# 4_FPGA.net
KiCad netlist of a schematic drawn in Altium Designer
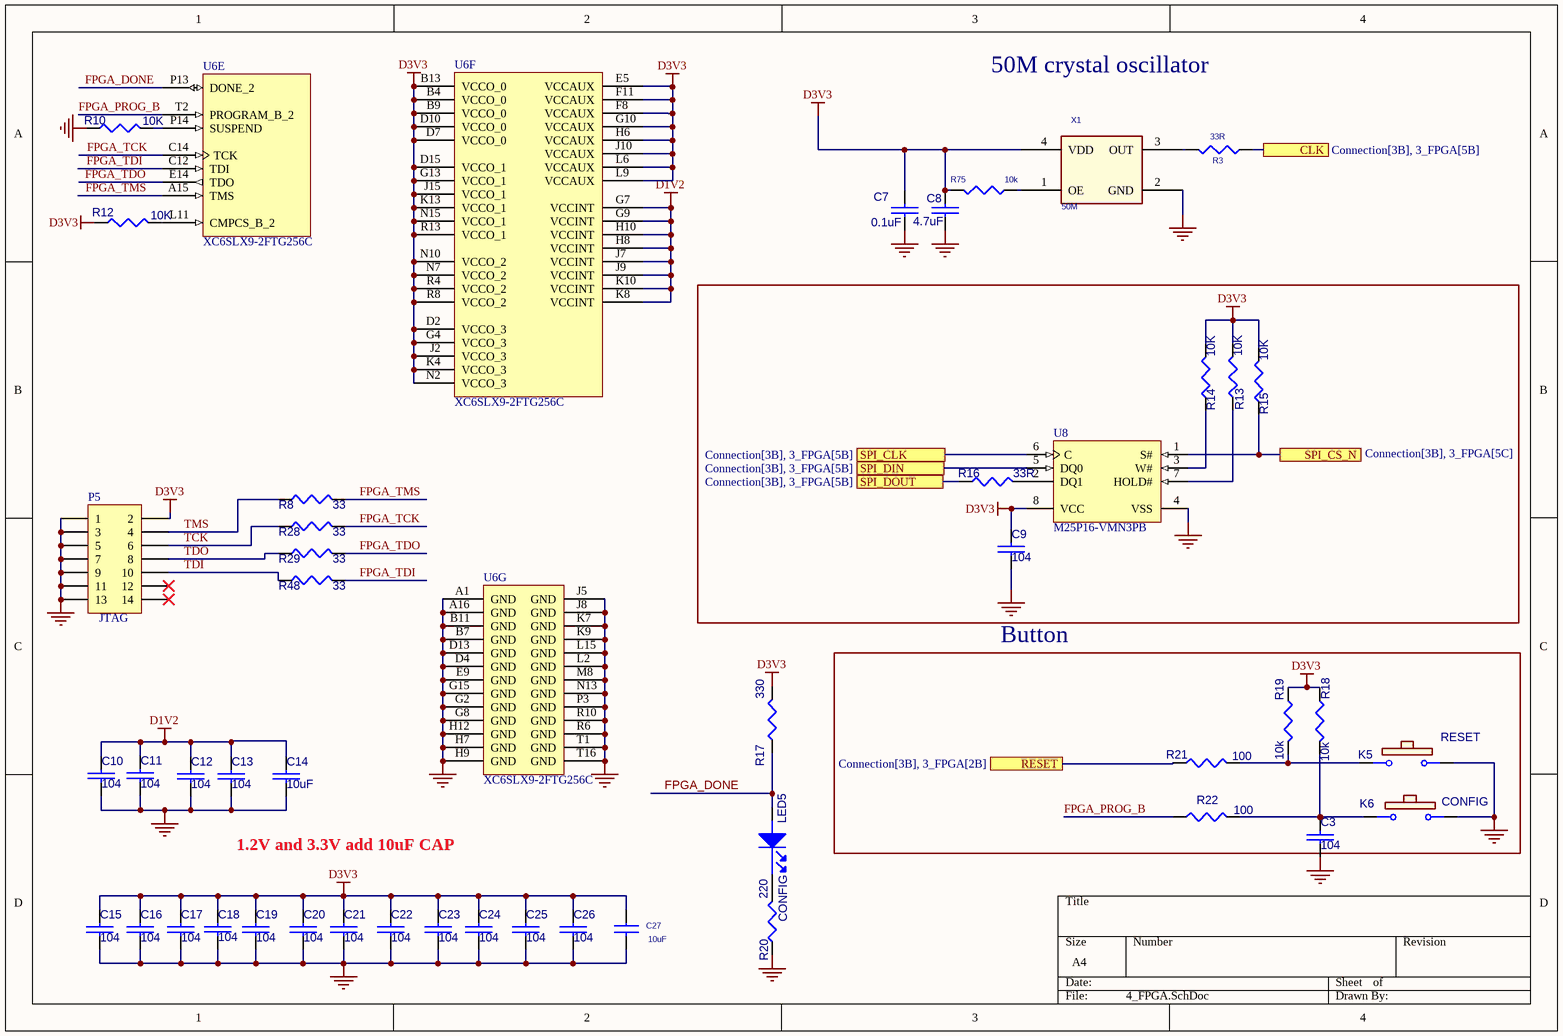
[diagram p0: 4_FPGA.SchDoc]

(export (version "E")
  (design (tool "Eeschema 10.0.6"))
  (components
    (comp (ref "C3") (value "104") (footprint "0402 Cap") (libsource (lib "SPARTAN6") (part "C_Dup2")))
    (comp (ref "C7") (value "0.1uF") (footprint "0402 Cap") (libsource (lib "SPARTAN6") (part "C_Dup2")))
    (comp (ref "C8") (value "4.7uF") (footprint "0402 Cap") (libsource (lib "SPARTAN6") (part "C_Dup2")))
    (comp (ref "C9") (value "104") (footprint "0402 Cap") (libsource (lib "SPARTAN6") (part "C_Dup2")))
    (comp (ref "C10") (value "104") (footprint "0402 Cap") (libsource (lib "SPARTAN6") (part "C_Dup2")))
    (comp (ref "C11") (value "104") (footprint "0402 Cap") (libsource (lib "SPARTAN6") (part "C_Dup2")))
    (comp (ref "C12") (value "104") (footprint "0402 Cap") (libsource (lib "SPARTAN6") (part "C_Dup2")))
    (comp (ref "C13") (value "104") (footprint "0402 Cap") (libsource (lib "SPARTAN6") (part "C_Dup2")))
    (comp (ref "C14") (value "10uF") (footprint "0402 Cap") (libsource (lib "SPARTAN6") (part "C_Dup2")))
    (comp (ref "C15") (value "104") (footprint "0402 Cap") (libsource (lib "SPARTAN6") (part "C_Dup2")))
    (comp (ref "C16") (value "104") (footprint "0402 Cap") (libsource (lib "SPARTAN6") (part "C_Dup2")))
    (comp (ref "C17") (value "104") (footprint "0402 Cap") (libsource (lib "SPARTAN6") (part "C_Dup2")))
    (comp (ref "C18") (value "104") (footprint "0402 Cap") (libsource (lib "SPARTAN6") (part "C_Dup2")))
    (comp (ref "C19") (value "104") (footprint "0402 Cap") (libsource (lib "SPARTAN6") (part "C_Dup2")))
    (comp (ref "C20") (value "104") (footprint "0402 Cap") (libsource (lib "SPARTAN6") (part "C_Dup2")))
    (comp (ref "C21") (value "104") (footprint "0402 Cap") (libsource (lib "SPARTAN6") (part "C_Dup2")))
    (comp (ref "C22") (value "104") (footprint "0402 Cap") (libsource (lib "SPARTAN6") (part "C_Dup2")))
    (comp (ref "C23") (value "104") (footprint "0402 Cap") (libsource (lib "SPARTAN6") (part "C_Dup2")))
    (comp (ref "C24") (value "104") (footprint "0402 Cap") (libsource (lib "SPARTAN6") (part "C_Dup2")))
    (comp (ref "C25") (value "104") (footprint "0402 Cap") (libsource (lib "SPARTAN6") (part "C_Dup2")))
    (comp (ref "C26") (value "104") (footprint "0402 Cap") (libsource (lib "SPARTAN6") (part "C_Dup2")))
    (comp (ref "C27")
      (value "10uF")
      (footprint "0805 Cap")
      (libsource (lib "SPARTAN6") (part "CAP NP_Dup2_1"))
    )
    (comp (ref "K5") (value "RESET") (footprint "KEY735SO") (libsource (lib "") (part "KEYB_1")))
    (comp (ref "K6") (value "CONFIG") (footprint "KEY735SO") (libsource (lib "*") (part "KEYB")))
    (comp (ref "LED5") (value "CONFIG") (footprint "LEDSO") (libsource (lib "*") (part "LED_Dup1")))
    (comp (ref "P5")
      (value "JTAG")
      (footprint "JTAG14-.5")
      (description "Header, 7-Pin, Dual row")
      (fields (field (name "PUBLISHER") "Altium Limited"))
      (libsource (lib "Miscellaneous Connectors") (part "Header 7X2"))
    )
    (comp (ref "R3") (value "33R") (libsource (lib "*") (part "RESISTOR")))
    (comp (ref "R8") (value "33") (libsource (lib "DB4-15") (part "R")))
    (comp (ref "R10") (value "10K") (libsource (lib "DB4-15") (part "R")))
    (comp (ref "R12") (value "10K") (libsource (lib "DB4-15") (part "R")))
    (comp (ref "R13") (value "10K") (libsource (lib "DB4-15") (part "R")))
    (comp (ref "R14") (value "10K") (libsource (lib "DB4-15") (part "R")))
    (comp (ref "R15") (value "10K") (libsource (lib "DB4-15") (part "R")))
    (comp (ref "R16") (value "33R") (footprint "0603") (libsource (lib "*") (part "R_Dup3")))
    (comp (ref "R17") (value "330") (footprint "0603") (libsource (lib "*") (part "R_Dup1")))
    (comp (ref "R18") (value "10k") (footprint "0603") (libsource (lib "*") (part "R_Dup2")))
    (comp (ref "R19") (value "10k") (footprint "0603") (libsource (lib "*") (part "R_Dup2")))
    (comp (ref "R20") (value "220") (footprint "0603") (libsource (lib "*") (part "R_Dup1")))
    (comp (ref "R21") (value "100") (footprint "0603") (libsource (lib "*") (part "R_Dup2")))
    (comp (ref "R22") (value "100") (footprint "0603") (libsource (lib "*") (part "R_Dup2")))
    (comp (ref "R28") (value "33") (libsource (lib "DB4-15") (part "R")))
    (comp (ref "R29") (value "33") (libsource (lib "DB4-15") (part "R")))
    (comp (ref "R48") (value "33") (libsource (lib "DB4-15") (part "R")))
    (comp (ref "R75") (value "10k") (libsource (lib "*") (part "RESISTOR")))
    (comp (ref "U6")
      (value "XC6SLX9-2FTG256C")
      (footprint "FTG256")
      (libsource (lib "Xilinx Spartan-6") (part "XC6SLX9-2FTG256C"))
    )
    (comp (ref "U8")
      (value "M25P16-VMN3PB")
      (footprint "SO8")
      (description "16 Mb (x1) Automotive Serial NOR Flash Memory, 75 MHz, 2.7 to 3.6 V, 8-pin SO8 Narrow (MN), Tube")
      (fields (field (name "VOLTAGE") "2.7V-3.6V爘ISHIDDEN=T") (field (name "MANUFACTURER") "Micron"))
      (libsource (lib "Micron Memory Serial NOR Flash") (part "M25P16-VMN3PB"))
    )
    (comp (ref "X1") (value "50M") (libsource (lib "*") (part "OSC")))
  )
  (nets
    (net (code "1") (name "/CLK") (class "Default")
      (node (ref "R3") (pin "1") (pinfunction "1_1") (pintype "passive"))
    )
    (net (code "2") (name "/FPGA_DONE") (class "Default")
      (node (ref "LED5") (pin "1") (pinfunction "ANODE_1") (pintype "passive"))
      (node (ref "R17") (pin "1") (pinfunction "1_1") (pintype "passive"))
      (node (ref "U6") (pin "P13") (pinfunction "DONE_2_P13") (pintype "bidirectional"))
    )
    (net (code "3") (name "/FPGA_PROG_B") (class "Default")
      (node (ref "R22") (pin "1") (pinfunction "1_1") (pintype "passive"))
      (node (ref "U6") (pin "T2") (pinfunction "PROGRAM_B_2_T2") (pintype "input"))
    )
    (net (code "4") (name "/FPGA_TCK") (class "Default")
      (node (ref "R28") (pin "2") (pinfunction "2_2") (pintype "passive"))
      (node (ref "U6") (pin "C14") (pinfunction "TCK_C14") (pintype "input"))
    )
    (net (code "5") (name "/FPGA_TDI") (class "Default")
      (node (ref "R48") (pin "2") (pinfunction "2_2") (pintype "passive"))
      (node (ref "U6") (pin "C12") (pinfunction "TDI_C12") (pintype "input"))
    )
    (net (code "6") (name "/FPGA_TDO") (class "Default")
      (node (ref "R29") (pin "2") (pinfunction "2_2") (pintype "passive"))
      (node (ref "U6") (pin "E14") (pinfunction "TDO_E14") (pintype "output"))
    )
    (net (code "7") (name "/FPGA_TMS") (class "Default")
      (node (ref "R8") (pin "2") (pinfunction "2_2") (pintype "passive"))
      (node (ref "U6") (pin "A15") (pinfunction "TMS_A15") (pintype "input"))
    )
    (net (code "8") (name "/RESET") (class "Default")
      (node (ref "R21") (pin "1") (pinfunction "1_1") (pintype "passive"))
    )
    (net (code "9") (name "/SPI_CLK") (class "Default")
      (node (ref "U8") (pin "6") (pinfunction "C_6") (pintype "input"))
    )
    (net (code "10") (name "/SPI_CS_N") (class "Default")
      (node (ref "R15") (pin "1") (pinfunction "1_1") (pintype "passive"))
      (node (ref "U8") (pin "1") (pinfunction "S#_1") (pintype "input"))
    )
    (net (code "11") (name "/SPI_DIN") (class "Default")
      (node (ref "U8") (pin "5") (pinfunction "DQ0_5") (pintype "input"))
    )
    (net (code "12") (name "/SPI_DOUT") (class "Default")
      (node (ref "R16") (pin "1") (pinfunction "1_1") (pintype "passive"))
    )
    (net (code "13") (name "/TCK") (class "Default")
      (node (ref "P5") (pin "6") (pinfunction "6_6") (pintype "passive"))
      (node (ref "R28") (pin "1") (pinfunction "1_1") (pintype "passive"))
    )
    (net (code "14") (name "/TDI") (class "Default")
      (node (ref "P5") (pin "10") (pinfunction "10_10") (pintype "passive"))
      (node (ref "R48") (pin "1") (pinfunction "1_1") (pintype "passive"))
    )
    (net (code "15") (name "/TDO") (class "Default")
      (node (ref "P5") (pin "8") (pinfunction "8_8") (pintype "passive"))
      (node (ref "R29") (pin "1") (pinfunction "1_1") (pintype "passive"))
    )
    (net (code "16") (name "/TMS") (class "Default")
      (node (ref "P5") (pin "4") (pinfunction "4_4") (pintype "passive"))
      (node (ref "R8") (pin "1") (pinfunction "1_1") (pintype "passive"))
    )
    (net (code "17") (name "D1V2") (class "Default")
      (node (ref "C10") (pin "1") (pinfunction "1_1") (pintype "passive"))
      (node (ref "C11") (pin "1") (pinfunction "1_1") (pintype "passive"))
      (node (ref "C12") (pin "1") (pinfunction "1_1") (pintype "passive"))
      (node (ref "C13") (pin "1") (pinfunction "1_1") (pintype "passive"))
      (node (ref "C14") (pin "1") (pinfunction "1_1") (pintype "passive"))
      (node (ref "U6") (pin "G7") (pinfunction "VCCINT_G7") (pintype "power_in"))
      (node (ref "U6") (pin "G9") (pinfunction "VCCINT_G9") (pintype "power_in"))
      (node (ref "U6") (pin "H10") (pinfunction "VCCINT_H10") (pintype "power_in"))
      (node (ref "U6") (pin "H8") (pinfunction "VCCINT_H8") (pintype "power_in"))
      (node (ref "U6") (pin "J7") (pinfunction "VCCINT_J7") (pintype "power_in"))
      (node (ref "U6") (pin "J9") (pinfunction "VCCINT_J9") (pintype "power_in"))
      (node (ref "U6") (pin "K10") (pinfunction "VCCINT_K10") (pintype "power_in"))
      (node (ref "U6") (pin "K8") (pinfunction "VCCINT_K8") (pintype "power_in"))
    )
    (net (code "18") (name "D3V3") (class "Default")
      (node (ref "C15") (pin "1") (pinfunction "1_1") (pintype "passive"))
      (node (ref "C16") (pin "1") (pinfunction "1_1") (pintype "passive"))
      (node (ref "C17") (pin "1") (pinfunction "1_1") (pintype "passive"))
      (node (ref "C18") (pin "1") (pinfunction "1_1") (pintype "passive"))
      (node (ref "C19") (pin "1") (pinfunction "1_1") (pintype "passive"))
      (node (ref "C20") (pin "1") (pinfunction "1_1") (pintype "passive"))
      (node (ref "C21") (pin "1") (pinfunction "1_1") (pintype "passive"))
      (node (ref "C22") (pin "1") (pinfunction "1_1") (pintype "passive"))
      (node (ref "C23") (pin "1") (pinfunction "1_1") (pintype "passive"))
      (node (ref "C24") (pin "1") (pinfunction "1_1") (pintype "passive"))
      (node (ref "C25") (pin "1") (pinfunction "1_1") (pintype "passive"))
      (node (ref "C26") (pin "1") (pinfunction "1_1") (pintype "passive"))
      (node (ref "C27") (pin "1") (pinfunction "1_1") (pintype "passive"))
      (node (ref "C7") (pin "1") (pinfunction "1_1") (pintype "passive"))
      (node (ref "C8") (pin "1") (pinfunction "1_1") (pintype "passive"))
      (node (ref "C9") (pin "1") (pinfunction "1_1") (pintype "passive"))
      (node (ref "P5") (pin "2") (pinfunction "2_2") (pintype "passive"))
      (node (ref "R12") (pin "1") (pinfunction "1_1") (pintype "passive"))
      (node (ref "R13") (pin "2") (pinfunction "2_2") (pintype "passive"))
      (node (ref "R14") (pin "2") (pinfunction "2_2") (pintype "passive"))
      (node (ref "R15") (pin "2") (pinfunction "2_2") (pintype "passive"))
      (node (ref "R17") (pin "2") (pinfunction "2_2") (pintype "passive"))
      (node (ref "R18") (pin "1") (pinfunction "1_1") (pintype "passive"))
      (node (ref "R19") (pin "1") (pinfunction "1_1") (pintype "passive"))
      (node (ref "R75") (pin "2") (pinfunction "2_2") (pintype "passive"))
      (node (ref "U6") (pin "B13") (pinfunction "VCCO_0_B13") (pintype "power_in"))
      (node (ref "U6") (pin "B4") (pinfunction "VCCO_0_B4") (pintype "power_in"))
      (node (ref "U6") (pin "B9") (pinfunction "VCCO_0_B9") (pintype "power_in"))
      (node (ref "U6") (pin "D10") (pinfunction "VCCO_0_D10") (pintype "power_in"))
      (node (ref "U6") (pin "D15") (pinfunction "VCCO_1_D15") (pintype "power_in"))
      (node (ref "U6") (pin "D2") (pinfunction "VCCO_3_D2") (pintype "power_in"))
      (node (ref "U6") (pin "D7") (pinfunction "VCCO_0_D7") (pintype "power_in"))
      (node (ref "U6") (pin "E5") (pinfunction "VCCAUX_E5") (pintype "power_in"))
      (node (ref "U6") (pin "F11") (pinfunction "VCCAUX_F11") (pintype "power_in"))
      (node (ref "U6") (pin "F8") (pinfunction "VCCAUX_F8") (pintype "power_in"))
      (node (ref "U6") (pin "G10") (pinfunction "VCCAUX_G10") (pintype "power_in"))
      (node (ref "U6") (pin "G13") (pinfunction "VCCO_1_G13") (pintype "power_in"))
      (node (ref "U6") (pin "G4") (pinfunction "VCCO_3_G4") (pintype "power_in"))
      (node (ref "U6") (pin "H6") (pinfunction "VCCAUX_H6") (pintype "power_in"))
      (node (ref "U6") (pin "J10") (pinfunction "VCCAUX_J10") (pintype "power_in"))
      (node (ref "U6") (pin "J15") (pinfunction "VCCO_1_J15") (pintype "power_in"))
      (node (ref "U6") (pin "J2") (pinfunction "VCCO_3_J2") (pintype "power_in"))
      (node (ref "U6") (pin "K13") (pinfunction "VCCO_1_K13") (pintype "power_in"))
      (node (ref "U6") (pin "K4") (pinfunction "VCCO_3_K4") (pintype "power_in"))
      (node (ref "U6") (pin "L6") (pinfunction "VCCAUX_L6") (pintype "power_in"))
      (node (ref "U6") (pin "L9") (pinfunction "VCCAUX_L9") (pintype "power_in"))
      (node (ref "U6") (pin "N10") (pinfunction "VCCO_2_N10") (pintype "power_in"))
      (node (ref "U6") (pin "N15") (pinfunction "VCCO_1_N15") (pintype "power_in"))
      (node (ref "U6") (pin "N2") (pinfunction "VCCO_3_N2") (pintype "power_in"))
      (node (ref "U6") (pin "N7") (pinfunction "VCCO_2_N7") (pintype "power_in"))
      (node (ref "U6") (pin "R13") (pinfunction "VCCO_1_R13") (pintype "power_in"))
      (node (ref "U6") (pin "R4") (pinfunction "VCCO_2_R4") (pintype "power_in"))
      (node (ref "U6") (pin "R8") (pinfunction "VCCO_2_R8") (pintype "power_in"))
      (node (ref "U8") (pin "8") (pinfunction "VCC_8") (pintype "power_in"))
      (node (ref "X1") (pin "4") (pinfunction "VDD_4") (pintype "passive"))
    )
    (net (code "19") (name "GND") (class "Default")
      (node (ref "C10") (pin "2") (pinfunction "2_2") (pintype "passive"))
      (node (ref "C11") (pin "2") (pinfunction "2_2") (pintype "passive"))
      (node (ref "C12") (pin "2") (pinfunction "2_2") (pintype "passive"))
      (node (ref "C13") (pin "2") (pinfunction "2_2") (pintype "passive"))
      (node (ref "C14") (pin "2") (pinfunction "2_2") (pintype "passive"))
      (node (ref "C15") (pin "2") (pinfunction "2_2") (pintype "passive"))
      (node (ref "C16") (pin "2") (pinfunction "2_2") (pintype "passive"))
      (node (ref "C17") (pin "2") (pinfunction "2_2") (pintype "passive"))
      (node (ref "C18") (pin "2") (pinfunction "2_2") (pintype "passive"))
      (node (ref "C19") (pin "2") (pinfunction "2_2") (pintype "passive"))
      (node (ref "C20") (pin "2") (pinfunction "2_2") (pintype "passive"))
      (node (ref "C21") (pin "2") (pinfunction "2_2") (pintype "passive"))
      (node (ref "C22") (pin "2") (pinfunction "2_2") (pintype "passive"))
      (node (ref "C23") (pin "2") (pinfunction "2_2") (pintype "passive"))
      (node (ref "C24") (pin "2") (pinfunction "2_2") (pintype "passive"))
      (node (ref "C25") (pin "2") (pinfunction "2_2") (pintype "passive"))
      (node (ref "C26") (pin "2") (pinfunction "2_2") (pintype "passive"))
      (node (ref "C27") (pin "2") (pinfunction "2_2") (pintype "passive"))
      (node (ref "C3") (pin "2") (pinfunction "2_2") (pintype "passive"))
      (node (ref "C7") (pin "2") (pinfunction "2_2") (pintype "passive"))
      (node (ref "C8") (pin "2") (pinfunction "2_2") (pintype "passive"))
      (node (ref "C9") (pin "2") (pinfunction "2_2") (pintype "passive"))
      (node (ref "K5") (pin "2") (pinfunction "2_2") (pintype "passive"))
      (node (ref "K6") (pin "1") (pinfunction "1_1") (pintype "passive"))
      (node (ref "P5") (pin "1") (pinfunction "1_1") (pintype "passive"))
      (node (ref "P5") (pin "11") (pinfunction "11_11") (pintype "passive"))
      (node (ref "P5") (pin "13") (pinfunction "13_13") (pintype "passive"))
      (node (ref "P5") (pin "3") (pinfunction "3_3") (pintype "passive"))
      (node (ref "P5") (pin "5") (pinfunction "5_5") (pintype "passive"))
      (node (ref "P5") (pin "7") (pinfunction "7_7") (pintype "passive"))
      (node (ref "P5") (pin "9") (pinfunction "9_9") (pintype "passive"))
      (node (ref "R10") (pin "1") (pinfunction "1_1") (pintype "passive"))
      (node (ref "R20") (pin "1") (pinfunction "1_1") (pintype "passive"))
      (node (ref "U6") (pin "A1") (pinfunction "GND_A1") (pintype "power_in"))
      (node (ref "U6") (pin "A16") (pinfunction "GND_A16") (pintype "power_in"))
      (node (ref "U6") (pin "B11") (pinfunction "GND_B11") (pintype "power_in"))
      (node (ref "U6") (pin "B7") (pinfunction "GND_B7") (pintype "power_in"))
      (node (ref "U6") (pin "D13") (pinfunction "GND_D13") (pintype "power_in"))
      (node (ref "U6") (pin "D4") (pinfunction "GND_D4") (pintype "power_in"))
      (node (ref "U6") (pin "E9") (pinfunction "GND_E9") (pintype "power_in"))
      (node (ref "U6") (pin "G15") (pinfunction "GND_G15") (pintype "power_in"))
      (node (ref "U6") (pin "G2") (pinfunction "GND_G2") (pintype "power_in"))
      (node (ref "U6") (pin "G8") (pinfunction "GND_G8") (pintype "power_in"))
      (node (ref "U6") (pin "H12") (pinfunction "GND_H12") (pintype "power_in"))
      (node (ref "U6") (pin "H7") (pinfunction "GND_H7") (pintype "power_in"))
      (node (ref "U6") (pin "H9") (pinfunction "GND_H9") (pintype "power_in"))
      (node (ref "U6") (pin "J5") (pinfunction "GND_J5") (pintype "power_in"))
      (node (ref "U6") (pin "J8") (pinfunction "GND_J8") (pintype "power_in"))
      (node (ref "U6") (pin "K7") (pinfunction "GND_K7") (pintype "power_in"))
      (node (ref "U6") (pin "K9") (pinfunction "GND_K9") (pintype "power_in"))
      (node (ref "U6") (pin "L15") (pinfunction "GND_L15") (pintype "power_in"))
      (node (ref "U6") (pin "L2") (pinfunction "GND_L2") (pintype "power_in"))
      (node (ref "U6") (pin "M8") (pinfunction "GND_M8") (pintype "power_in"))
      (node (ref "U6") (pin "N13") (pinfunction "GND_N13") (pintype "power_in"))
      (node (ref "U6") (pin "P3") (pinfunction "GND_P3") (pintype "power_in"))
      (node (ref "U6") (pin "R10") (pinfunction "GND_R10") (pintype "power_in"))
      (node (ref "U6") (pin "R6") (pinfunction "GND_R6") (pintype "power_in"))
      (node (ref "U6") (pin "T1") (pinfunction "GND_T1") (pintype "power_in"))
      (node (ref "U6") (pin "T16") (pinfunction "GND_T16") (pintype "power_in"))
      (node (ref "U8") (pin "4") (pinfunction "VSS_4") (pintype "power_in"))
      (node (ref "X1") (pin "2") (pinfunction "GND_2") (pintype "passive"))
    )
    (net (code "20") (name "Net-(C3-Pad1)") (class "Default")
      (node (ref "C3") (pin "1") (pinfunction "1_1") (pintype "passive"))
      (node (ref "K6") (pin "2") (pinfunction "2_2") (pintype "passive"))
      (node (ref "R18") (pin "2") (pinfunction "2_2") (pintype "passive"))
      (node (ref "R22") (pin "2") (pinfunction "2_2") (pintype "passive"))
    )
    (net (code "21") (name "Net-(K5-Pad1)") (class "Default")
      (node (ref "K5") (pin "1") (pinfunction "1_1") (pintype "passive"))
      (node (ref "R19") (pin "2") (pinfunction "2_2") (pintype "passive"))
      (node (ref "R21") (pin "2") (pinfunction "2_2") (pintype "passive"))
    )
    (net (code "22") (name "Net-(LED5-CATHODE)") (class "Default")
      (node (ref "LED5") (pin "2") (pinfunction "CATHODE_2") (pintype "passive"))
      (node (ref "R20") (pin "2") (pinfunction "2_2") (pintype "passive"))
    )
    (net (code "23") (name "Net-(U6E-CMPCS_B_2)") (class "Default")
      (node (ref "R12") (pin "2") (pinfunction "2_2") (pintype "passive"))
      (node (ref "U6") (pin "L11") (pinfunction "CMPCS_B_2_L11") (pintype "input"))
    )
    (net (code "24") (name "Net-(U6E-SUSPEND)") (class "Default")
      (node (ref "R10") (pin "2") (pinfunction "2_2") (pintype "passive"))
      (node (ref "U6") (pin "P14") (pinfunction "SUSPEND_P14") (pintype "input"))
    )
    (net (code "25") (name "Net-(U8-DQ1)") (class "Default")
      (node (ref "R16") (pin "2") (pinfunction "2_2") (pintype "passive"))
      (node (ref "U8") (pin "2") (pinfunction "DQ1_2") (pintype "tri_state"))
    )
    (net (code "26") (name "Net-(U8-HOLD#)") (class "Default")
      (node (ref "R13") (pin "1") (pinfunction "1_1") (pintype "passive"))
      (node (ref "U8") (pin "7") (pinfunction "HOLD#_7") (pintype "input"))
    )
    (net (code "27") (name "Net-(U8-W#)") (class "Default")
      (node (ref "R14") (pin "1") (pinfunction "1_1") (pintype "passive"))
      (node (ref "U8") (pin "3") (pinfunction "W#_3") (pintype "input"))
    )
    (net (code "28") (name "Net-(X1-OE)") (class "Default")
      (node (ref "R75") (pin "1") (pinfunction "1_1") (pintype "passive"))
      (node (ref "X1") (pin "1") (pinfunction "OE_1") (pintype "passive"))
    )
    (net (code "29") (name "Net-(X1-OUT)") (class "Default")
      (node (ref "R3") (pin "2") (pinfunction "2_2") (pintype "passive"))
      (node (ref "X1") (pin "3") (pinfunction "OUT_3") (pintype "passive"))
    )
    (net (code "30") (name "unconnected-(P5-Pad12)") (class "Default")
      (node (ref "P5") (pin "12") (pinfunction "12_12") (pintype "passive+no_connect"))
    )
    (net (code "31") (name "unconnected-(P5-Pad14)") (class "Default")
      (node (ref "P5") (pin "14") (pinfunction "14_14") (pintype "passive+no_connect"))
    )
  )
)
